# prog.net
KiCad netlist of a schematic drawn in EAGLE
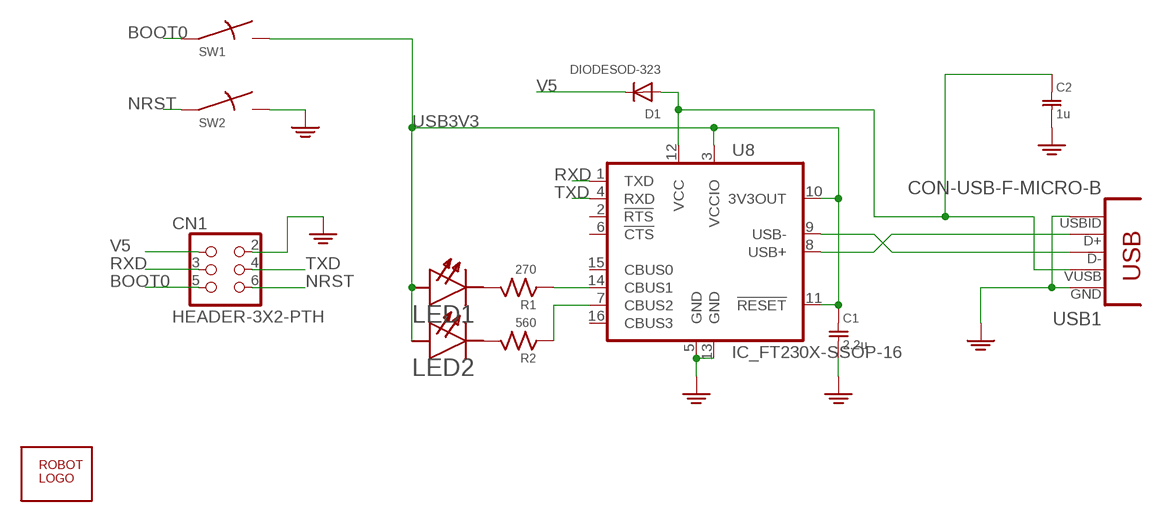
[diagram p0: schematic, sheet 1]

(export (version "E")
  (design (tool "Eeschema 10.0.6"))
  (components
    (comp (ref "C1")
      (value "2.2u")
      (footprint "eagle-import:SMD0603")
      (libsource (lib "eagle-import") (part "C0603"))
    )
    (comp (ref "C2")
      (value "1u")
      (footprint "eagle-import:SMD0603")
      (libsource (lib "eagle-import") (part "C0603"))
    )
    (comp (ref "CN1")
      (value "HEADER-3X2-PTH")
      (footprint "eagle-import:HEADER-3X2-PTH")
      (libsource (lib "eagle-import") (part "HEADER-3X2-PTH"))
    )
    (comp (ref "D1")
      (value "DIODESOD-323")
      (footprint "eagle-import:SOD-323")
      (libsource (lib "eagle-import") (part "DIODESOD-323"))
    )
    (comp (ref "LED1")
      (value "GREEN")
      (footprint "eagle-import:SMD0603D")
      (libsource (lib "eagle-import") (part "LED"))
    )
    (comp (ref "LED2")
      (value "ORANGE")
      (footprint "eagle-import:SMD0603D")
      (libsource (lib "eagle-import") (part "LED"))
    )
    (comp (ref "R1")
      (value "270")
      (footprint "eagle-import:SMD0603")
      (libsource (lib "eagle-import") (part "R0603"))
    )
    (comp (ref "R2")
      (value "560")
      (footprint "eagle-import:SMD0603")
      (libsource (lib "eagle-import") (part "R0603"))
    )
    (comp (ref "SW1")
      (value "SWITCHKMR211")
      (footprint "eagle-import:KMR211")
      (libsource (lib "eagle-import") (part "SWITCHKMR211"))
    )
    (comp (ref "SW2")
      (value "SWITCHKMR211")
      (footprint "eagle-import:KMR211")
      (libsource (lib "eagle-import") (part "SWITCHKMR211"))
    )
    (comp (ref "U$1")
      (value "ROBOTMAN-LOGO")
      (footprint "eagle-import:ROBOTMAN-LOGO")
      (libsource (lib "eagle-import") (part "ROBOTMAN-LOGO"))
    )
    (comp (ref "U8")
      (value "IC_FT230X-SSOP-16")
      (footprint "eagle-import:SSOP-16-FTDI")
      (libsource (lib "eagle-import") (part "IC_FT230X-SSOP-16"))
    )
    (comp (ref "USB1")
      (value "CON-USB-F-MICRO-B")
      (footprint "eagle-import:CONN_USB_MICRO-B")
      (libsource (lib "eagle-import") (part "CON-USB-F-MICRO-B"))
    )
  )
  (nets
    (net (code "1") (name "/BOOT0") (class "Default")
      (node (ref "CN1") (pin "5") (pinfunction "P$5_5") (pintype "passive"))
      (node (ref "SW1") (pin "1") (pinfunction "P$1_1") (pintype "passive"))
      (node (ref "SW1") (pin "3") (pinfunction "P$1_3") (pintype "passive"))
    )
    (net (code "2") (name "/NRST") (class "Default")
      (node (ref "CN1") (pin "6") (pinfunction "P$6_6") (pintype "passive"))
      (node (ref "SW2") (pin "1") (pinfunction "P$1_1") (pintype "passive"))
      (node (ref "SW2") (pin "3") (pinfunction "P$1_3") (pintype "passive"))
    )
    (net (code "3") (name "/RXD") (class "Default")
      (node (ref "CN1") (pin "3") (pinfunction "P$3_3") (pintype "passive"))
      (node (ref "U8") (pin "1") (pinfunction "TXD_1") (pintype "output"))
    )
    (net (code "4") (name "/TXD") (class "Default")
      (node (ref "CN1") (pin "4") (pinfunction "P$4_4") (pintype "passive"))
      (node (ref "U8") (pin "4") (pinfunction "RXD_4") (pintype "input"))
    )
    (net (code "5") (name "/USB3V3") (class "Default")
      (node (ref "C1") (pin "1") (pinfunction "P$1_1") (pintype "passive"))
      (node (ref "LED1") (pin "A") (pinfunction "A_A") (pintype "passive"))
      (node (ref "LED2") (pin "A") (pinfunction "A_A") (pintype "passive"))
      (node (ref "SW1") (pin "2") (pinfunction "P$2_2") (pintype "passive"))
      (node (ref "SW1") (pin "4") (pinfunction "P$2_4") (pintype "passive"))
      (node (ref "U8") (pin "10") (pinfunction "3V3OUT_10") (pintype "power_in"))
      (node (ref "U8") (pin "11") (pinfunction "~{RESET}_11") (pintype "bidirectional"))
      (node (ref "U8") (pin "3") (pinfunction "VCCIO_3") (pintype "power_in"))
    )
    (net (code "6") (name "/V5") (class "Default")
      (node (ref "CN1") (pin "1") (pinfunction "P$1_1") (pintype "passive"))
      (node (ref "D1") (pin "C") (pinfunction "C_C") (pintype "passive"))
    )
    (net (code "7") (name "Net-(C2-P$1)") (class "Default")
      (node (ref "C2") (pin "1") (pinfunction "P$1_1") (pintype "passive"))
      (node (ref "D1") (pin "A") (pinfunction "A_A") (pintype "passive"))
      (node (ref "U8") (pin "12") (pinfunction "VCC_12") (pintype "power_in"))
      (node (ref "USB1") (pin "P1") (pinfunction "VUSB_P1") (pintype "bidirectional"))
    )
    (net (code "8") (name "Net-(R1-P$1)") (class "Default")
      (node (ref "R1") (pin "1") (pinfunction "P$1_1") (pintype "passive"))
      (node (ref "U8") (pin "14") (pinfunction "CBUS1_14") (pintype "bidirectional"))
    )
    (net (code "9") (name "Net-(R1-P$2)") (class "Default")
      (node (ref "LED1") (pin "C") (pinfunction "C_C") (pintype "passive"))
      (node (ref "R1") (pin "2") (pinfunction "P$2_2") (pintype "passive"))
    )
    (net (code "10") (name "Net-(R2-P$1)") (class "Default")
      (node (ref "R2") (pin "1") (pinfunction "P$1_1") (pintype "passive"))
      (node (ref "U8") (pin "7") (pinfunction "CBUS2_7") (pintype "bidirectional"))
    )
    (net (code "11") (name "Net-(R2-P$2)") (class "Default")
      (node (ref "LED2") (pin "C") (pinfunction "C_C") (pintype "passive"))
      (node (ref "R2") (pin "2") (pinfunction "P$2_2") (pintype "passive"))
    )
    (net (code "12") (name "Net-(U8-USB+)") (class "Default")
      (node (ref "U8") (pin "8") (pinfunction "USB+_8") (pintype "output"))
      (node (ref "USB1") (pin "P3") (pinfunction "D+_P3") (pintype "bidirectional"))
    )
    (net (code "13") (name "Net-(U8-USB-)") (class "Default")
      (node (ref "U8") (pin "9") (pinfunction "USB-_9") (pintype "input"))
      (node (ref "USB1") (pin "P2") (pinfunction "D-_P2") (pintype "bidirectional"))
    )
    (net (code "14") (name "PWR-GND") (class "Default")
      (node (ref "C1") (pin "2") (pinfunction "P$2_2") (pintype "passive"))
      (node (ref "C2") (pin "2") (pinfunction "P$2_2") (pintype "passive"))
      (node (ref "CN1") (pin "2") (pinfunction "P$2_2") (pintype "passive"))
      (node (ref "SW2") (pin "2") (pinfunction "P$2_2") (pintype "passive"))
      (node (ref "SW2") (pin "4") (pinfunction "P$2_4") (pintype "passive"))
      (node (ref "U8") (pin "13") (pinfunction "GND_13") (pintype "power_in"))
      (node (ref "U8") (pin "5") (pinfunction "GND_5") (pintype "power_in"))
      (node (ref "USB1") (pin "P4") (pinfunction "USBID_P4") (pintype "bidirectional"))
      (node (ref "USB1") (pin "P5") (pinfunction "GND_P5") (pintype "bidirectional"))
    )
    (net (code "15") (name "unconnected-(U8-CBUS0-Pad15)") (class "Default")
      (node (ref "U8") (pin "15") (pinfunction "CBUS0_15") (pintype "bidirectional"))
    )
    (net (code "16") (name "unconnected-(U8-CBUS3-Pad16)") (class "Default")
      (node (ref "U8") (pin "16") (pinfunction "CBUS3_16") (pintype "bidirectional"))
    )
    (net (code "17") (name "unconnected-(U8-~{CTS}-Pad6)") (class "Default")
      (node (ref "U8") (pin "6") (pinfunction "~{CTS}_6") (pintype "bidirectional"))
    )
    (net (code "18") (name "unconnected-(U8-~{RTS}-Pad2)") (class "Default")
      (node (ref "U8") (pin "2") (pinfunction "~{RTS}_2") (pintype "bidirectional"))
    )
  )
)
